# Arm_V4.net
KiCad netlist of a schematic drawn in EAGLE
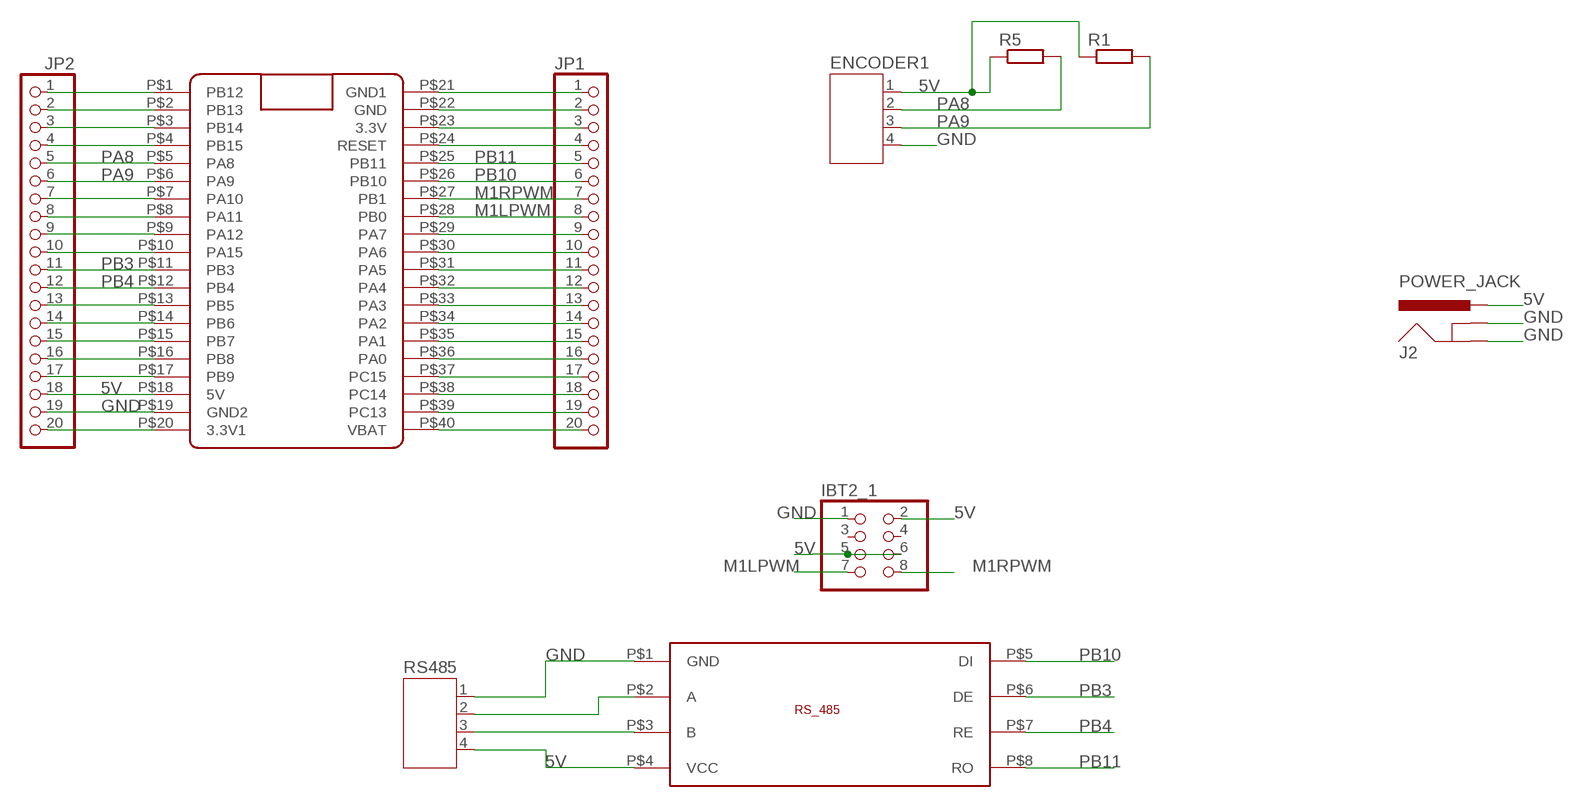
[diagram p0: schematic, sheet 1]

(export (version "E")
  (design (tool "Eeschema 10.0.6"))
  (components
    (comp (ref "ENCODER1")
      (value "JST-PH4")
      (footprint "eagle-import:JST-PH4")
      (libsource (lib "eagle-import") (part "JST-PH4"))
    )
    (comp (ref "IBT2_1")
      (value "PINHD-2X4")
      (footprint "eagle-import:2X04")
      (libsource (lib "eagle-import") (part "PINHD-2X4"))
    )
    (comp (ref "J2")
      (value "POWER_JACK")
      (footprint "eagle-import:POWER_JACK")
      (fields (field (name "MPN") "PJ-202A"))
      (libsource (lib "eagle-import") (part "POWER_JACK"))
    )
    (comp (ref "JP1")
      (value "PINHD-1X20")
      (footprint "eagle-import:1X20")
      (libsource (lib "eagle-import") (part "PINHD-1X20"))
    )
    (comp (ref "JP2")
      (value "PINHD-1X20")
      (footprint "eagle-import:1X20")
      (libsource (lib "eagle-import") (part "PINHD-1X20"))
    )
    (comp (ref "R1")
      (value "R-EU_0207/10")
      (footprint "eagle-import:0207_10")
      (libsource (lib "eagle-import") (part "R-EU_0207/10"))
    )
    (comp (ref "R5")
      (value "R-EU_0207/10")
      (footprint "eagle-import:0207_10")
      (libsource (lib "eagle-import") (part "R-EU_0207/10"))
    )
    (comp (ref "RS485")
      (value "JST-PH4")
      (footprint "eagle-import:JST-PH4")
      (libsource (lib "eagle-import") (part "JST-PH4"))
    )
    (comp (ref "U$1")
      (value "BLUE_PILL")
      (footprint "eagle-import:BLUE_PILL")
      (libsource (lib "eagle-import") (part "BLUE_PILL"))
    )
    (comp (ref "U$2")
      (value "RS_485PCB")
      (footprint "eagle-import:RSS485PCB")
      (libsource (lib "eagle-import") (part "RS_485PCB"))
    )
  )
  (nets
    (net (code "1") (name "/5V") (class "Default")
      (node (ref "ENCODER1") (pin "1") (pinfunction "1_1") (pintype "passive"))
      (node (ref "IBT2_1") (pin "2") (pinfunction "2_2") (pintype "passive"))
      (node (ref "IBT2_1") (pin "5") (pinfunction "5_5") (pintype "passive"))
      (node (ref "IBT2_1") (pin "6") (pinfunction "6_6") (pintype "passive"))
      (node (ref "J2") (pin "PWR") (pinfunction "PWR_PWR") (pintype "bidirectional"))
      (node (ref "JP2") (pin "18") (pinfunction "18_18") (pintype "passive"))
      (node (ref "R1") (pin "1") (pinfunction "1_1") (pintype "passive"))
      (node (ref "R5") (pin "1") (pinfunction "1_1") (pintype "passive"))
      (node (ref "RS485") (pin "4") (pinfunction "4_4") (pintype "passive"))
      (node (ref "U$1") (pin "P$18") (pinfunction "5V_P$18") (pintype "bidirectional"))
      (node (ref "U$2") (pin "P$4") (pinfunction "VCC_P$4") (pintype "bidirectional"))
    )
    (net (code "2") (name "/GND") (class "Default")
      (node (ref "ENCODER1") (pin "4") (pinfunction "4_4") (pintype "passive"))
      (node (ref "IBT2_1") (pin "1") (pinfunction "1_1") (pintype "passive"))
      (node (ref "J2") (pin "GNDBREAK") (pinfunction "GNDBREAK_GNDBREAK") (pintype "bidirectional"))
      (node (ref "JP2") (pin "19") (pinfunction "19_19") (pintype "passive"))
      (node (ref "RS485") (pin "1") (pinfunction "1_1") (pintype "passive"))
      (node (ref "U$1") (pin "P$19") (pinfunction "GND2_P$19") (pintype "bidirectional"))
      (node (ref "U$2") (pin "P$1") (pinfunction "GND_P$1") (pintype "bidirectional"))
    )
    (net (code "3") (name "/M1LPWM") (class "Default")
      (node (ref "IBT2_1") (pin "7") (pinfunction "7_7") (pintype "passive"))
      (node (ref "JP1") (pin "8") (pinfunction "8_8") (pintype "passive"))
      (node (ref "U$1") (pin "P$28") (pinfunction "PB0_P$28") (pintype "bidirectional"))
    )
    (net (code "4") (name "/M1RPWM") (class "Default")
      (node (ref "IBT2_1") (pin "8") (pinfunction "8_8") (pintype "passive"))
      (node (ref "JP1") (pin "7") (pinfunction "7_7") (pintype "passive"))
      (node (ref "U$1") (pin "P$27") (pinfunction "PB1_P$27") (pintype "bidirectional"))
    )
    (net (code "5") (name "/PA8") (class "Default")
      (node (ref "ENCODER1") (pin "2") (pinfunction "2_2") (pintype "passive"))
      (node (ref "JP2") (pin "5") (pinfunction "5_5") (pintype "passive"))
      (node (ref "R5") (pin "2") (pinfunction "2_2") (pintype "passive"))
      (node (ref "U$1") (pin "P$5") (pinfunction "PA8_P$5") (pintype "bidirectional"))
    )
    (net (code "6") (name "/PA9") (class "Default")
      (node (ref "ENCODER1") (pin "3") (pinfunction "3_3") (pintype "passive"))
      (node (ref "JP2") (pin "6") (pinfunction "6_6") (pintype "passive"))
      (node (ref "R1") (pin "2") (pinfunction "2_2") (pintype "passive"))
      (node (ref "U$1") (pin "P$6") (pinfunction "PA9_P$6") (pintype "bidirectional"))
    )
    (net (code "7") (name "/PB3") (class "Default")
      (node (ref "JP2") (pin "11") (pinfunction "11_11") (pintype "passive"))
      (node (ref "U$1") (pin "P$11") (pinfunction "PB3_P$11") (pintype "bidirectional"))
      (node (ref "U$2") (pin "P$6") (pinfunction "DE_P$6") (pintype "bidirectional"))
    )
    (net (code "8") (name "/PB4") (class "Default")
      (node (ref "JP2") (pin "12") (pinfunction "12_12") (pintype "passive"))
      (node (ref "U$1") (pin "P$12") (pinfunction "PB4_P$12") (pintype "bidirectional"))
      (node (ref "U$2") (pin "P$7") (pinfunction "RE_P$7") (pintype "bidirectional"))
    )
    (net (code "9") (name "/PB10") (class "Default")
      (node (ref "JP1") (pin "6") (pinfunction "6_6") (pintype "passive"))
      (node (ref "U$1") (pin "P$26") (pinfunction "PB10_P$26") (pintype "bidirectional"))
      (node (ref "U$2") (pin "P$5") (pinfunction "DI_P$5") (pintype "bidirectional"))
    )
    (net (code "10") (name "/PB11") (class "Default")
      (node (ref "JP1") (pin "5") (pinfunction "5_5") (pintype "passive"))
      (node (ref "U$1") (pin "P$25") (pinfunction "PB11_P$25") (pintype "bidirectional"))
      (node (ref "U$2") (pin "P$8") (pinfunction "RO_P$8") (pintype "bidirectional"))
    )
    (net (code "11") (name "Net-(U$1-3.3V)") (class "Default")
      (node (ref "JP1") (pin "3") (pinfunction "3_3") (pintype "passive"))
      (node (ref "U$1") (pin "P$23") (pinfunction "3.3V_P$23") (pintype "bidirectional"))
    )
    (net (code "12") (name "Net-(U$1-3.3V1)") (class "Default")
      (node (ref "JP2") (pin "20") (pinfunction "20_20") (pintype "passive"))
      (node (ref "U$1") (pin "P$20") (pinfunction "3.3V1_P$20") (pintype "bidirectional"))
    )
    (net (code "13") (name "Net-(U$1-GND)") (class "Default")
      (node (ref "JP1") (pin "2") (pinfunction "2_2") (pintype "passive"))
      (node (ref "U$1") (pin "P$22") (pinfunction "GND_P$22") (pintype "bidirectional"))
    )
    (net (code "14") (name "Net-(U$1-GND1)") (class "Default")
      (node (ref "JP1") (pin "1") (pinfunction "1_1") (pintype "passive"))
      (node (ref "U$1") (pin "P$21") (pinfunction "GND1_P$21") (pintype "power_in"))
    )
    (net (code "15") (name "Net-(U$1-PA0)") (class "Default")
      (node (ref "JP1") (pin "16") (pinfunction "16_16") (pintype "passive"))
      (node (ref "U$1") (pin "P$36") (pinfunction "PA0_P$36") (pintype "bidirectional"))
    )
    (net (code "16") (name "Net-(U$1-PA1)") (class "Default")
      (node (ref "JP1") (pin "15") (pinfunction "15_15") (pintype "passive"))
      (node (ref "U$1") (pin "P$35") (pinfunction "PA1_P$35") (pintype "bidirectional"))
    )
    (net (code "17") (name "Net-(U$1-PA2)") (class "Default")
      (node (ref "JP1") (pin "14") (pinfunction "14_14") (pintype "passive"))
      (node (ref "U$1") (pin "P$34") (pinfunction "PA2_P$34") (pintype "bidirectional"))
    )
    (net (code "18") (name "Net-(U$1-PA3)") (class "Default")
      (node (ref "JP1") (pin "13") (pinfunction "13_13") (pintype "passive"))
      (node (ref "U$1") (pin "P$33") (pinfunction "PA3_P$33") (pintype "bidirectional"))
    )
    (net (code "19") (name "Net-(U$1-PA4)") (class "Default")
      (node (ref "JP1") (pin "12") (pinfunction "12_12") (pintype "passive"))
      (node (ref "U$1") (pin "P$32") (pinfunction "PA4_P$32") (pintype "bidirectional"))
    )
    (net (code "20") (name "Net-(U$1-PA5)") (class "Default")
      (node (ref "JP1") (pin "11") (pinfunction "11_11") (pintype "passive"))
      (node (ref "U$1") (pin "P$31") (pinfunction "PA5_P$31") (pintype "bidirectional"))
    )
    (net (code "21") (name "Net-(U$1-PA6)") (class "Default")
      (node (ref "JP1") (pin "10") (pinfunction "10_10") (pintype "passive"))
      (node (ref "U$1") (pin "P$30") (pinfunction "PA6_P$30") (pintype "bidirectional"))
    )
    (net (code "22") (name "Net-(U$1-PA7)") (class "Default")
      (node (ref "JP1") (pin "9") (pinfunction "9_9") (pintype "passive"))
      (node (ref "U$1") (pin "P$29") (pinfunction "PA7_P$29") (pintype "bidirectional"))
    )
    (net (code "23") (name "Net-(U$1-PA10)") (class "Default")
      (node (ref "JP2") (pin "7") (pinfunction "7_7") (pintype "passive"))
      (node (ref "U$1") (pin "P$7") (pinfunction "PA10_P$7") (pintype "bidirectional"))
    )
    (net (code "24") (name "Net-(U$1-PA11)") (class "Default")
      (node (ref "JP2") (pin "8") (pinfunction "8_8") (pintype "passive"))
      (node (ref "U$1") (pin "P$8") (pinfunction "PA11_P$8") (pintype "bidirectional"))
    )
    (net (code "25") (name "Net-(U$1-PA12)") (class "Default")
      (node (ref "JP2") (pin "9") (pinfunction "9_9") (pintype "passive"))
      (node (ref "U$1") (pin "P$9") (pinfunction "PA12_P$9") (pintype "bidirectional"))
    )
    (net (code "26") (name "Net-(U$1-PA15)") (class "Default")
      (node (ref "JP2") (pin "10") (pinfunction "10_10") (pintype "passive"))
      (node (ref "U$1") (pin "P$10") (pinfunction "PA15_P$10") (pintype "bidirectional"))
    )
    (net (code "27") (name "Net-(U$1-PB5)") (class "Default")
      (node (ref "JP2") (pin "13") (pinfunction "13_13") (pintype "passive"))
      (node (ref "U$1") (pin "P$13") (pinfunction "PB5_P$13") (pintype "bidirectional"))
    )
    (net (code "28") (name "Net-(U$1-PB6)") (class "Default")
      (node (ref "JP2") (pin "14") (pinfunction "14_14") (pintype "passive"))
      (node (ref "U$1") (pin "P$14") (pinfunction "PB6_P$14") (pintype "bidirectional"))
    )
    (net (code "29") (name "Net-(U$1-PB7)") (class "Default")
      (node (ref "JP2") (pin "15") (pinfunction "15_15") (pintype "passive"))
      (node (ref "U$1") (pin "P$15") (pinfunction "PB7_P$15") (pintype "bidirectional"))
    )
    (net (code "30") (name "Net-(U$1-PB8)") (class "Default")
      (node (ref "JP2") (pin "16") (pinfunction "16_16") (pintype "passive"))
      (node (ref "U$1") (pin "P$16") (pinfunction "PB8_P$16") (pintype "bidirectional"))
    )
    (net (code "31") (name "Net-(U$1-PB9)") (class "Default")
      (node (ref "JP2") (pin "17") (pinfunction "17_17") (pintype "passive"))
      (node (ref "U$1") (pin "P$17") (pinfunction "PB9_P$17") (pintype "bidirectional"))
    )
    (net (code "32") (name "Net-(U$1-PB12)") (class "Default")
      (node (ref "JP2") (pin "1") (pinfunction "1_1") (pintype "passive"))
      (node (ref "U$1") (pin "P$1") (pinfunction "PB12_P$1") (pintype "bidirectional"))
    )
    (net (code "33") (name "Net-(U$1-PB13)") (class "Default")
      (node (ref "JP2") (pin "2") (pinfunction "2_2") (pintype "passive"))
      (node (ref "U$1") (pin "P$2") (pinfunction "PB13_P$2") (pintype "bidirectional"))
    )
    (net (code "34") (name "Net-(U$1-PB14)") (class "Default")
      (node (ref "JP2") (pin "3") (pinfunction "3_3") (pintype "passive"))
      (node (ref "U$1") (pin "P$3") (pinfunction "PB14_P$3") (pintype "bidirectional"))
    )
    (net (code "35") (name "Net-(U$1-PB15)") (class "Default")
      (node (ref "JP2") (pin "4") (pinfunction "4_4") (pintype "passive"))
      (node (ref "U$1") (pin "P$4") (pinfunction "PB15_P$4") (pintype "bidirectional"))
    )
    (net (code "36") (name "Net-(U$1-PC13)") (class "Default")
      (node (ref "JP1") (pin "19") (pinfunction "19_19") (pintype "passive"))
      (node (ref "U$1") (pin "P$39") (pinfunction "PC13_P$39") (pintype "bidirectional"))
    )
    (net (code "37") (name "Net-(U$1-PC14)") (class "Default")
      (node (ref "JP1") (pin "18") (pinfunction "18_18") (pintype "passive"))
      (node (ref "U$1") (pin "P$38") (pinfunction "PC14_P$38") (pintype "bidirectional"))
    )
    (net (code "38") (name "Net-(U$1-PC15)") (class "Default")
      (node (ref "JP1") (pin "17") (pinfunction "17_17") (pintype "passive"))
      (node (ref "U$1") (pin "P$37") (pinfunction "PC15_P$37") (pintype "bidirectional"))
    )
    (net (code "39") (name "Net-(U$1-RESET)") (class "Default")
      (node (ref "JP1") (pin "4") (pinfunction "4_4") (pintype "passive"))
      (node (ref "U$1") (pin "P$24") (pinfunction "RESET_P$24") (pintype "bidirectional"))
    )
    (net (code "40") (name "Net-(U$1-VBAT)") (class "Default")
      (node (ref "JP1") (pin "20") (pinfunction "20_20") (pintype "passive"))
      (node (ref "U$1") (pin "P$40") (pinfunction "VBAT_P$40") (pintype "bidirectional"))
    )
    (net (code "41") (name "Net-(U$2-A)") (class "Default")
      (node (ref "RS485") (pin "2") (pinfunction "2_2") (pintype "passive"))
      (node (ref "U$2") (pin "P$2") (pinfunction "A_P$2") (pintype "bidirectional"))
    )
    (net (code "42") (name "Net-(U$2-B)") (class "Default")
      (node (ref "RS485") (pin "3") (pinfunction "3_3") (pintype "passive"))
      (node (ref "U$2") (pin "P$3") (pinfunction "B_P$3") (pintype "bidirectional"))
    )
    (net (code "43") (name "unconnected-(IBT2_1-Pad3)") (class "Default")
      (node (ref "IBT2_1") (pin "3") (pinfunction "3_3") (pintype "passive"))
    )
    (net (code "44") (name "unconnected-(IBT2_1-Pad4)") (class "Default")
      (node (ref "IBT2_1") (pin "4") (pinfunction "4_4") (pintype "passive"))
    )
    (net (code "45") (name "unconnected-(J2-PadGND)") (class "Default")
      (node (ref "J2") (pin "GND") (pinfunction "GND_GND") (pintype "bidirectional"))
    )
  )
)
